# shield_puissance.net
KiCad netlist of a schematic drawn in EAGLE
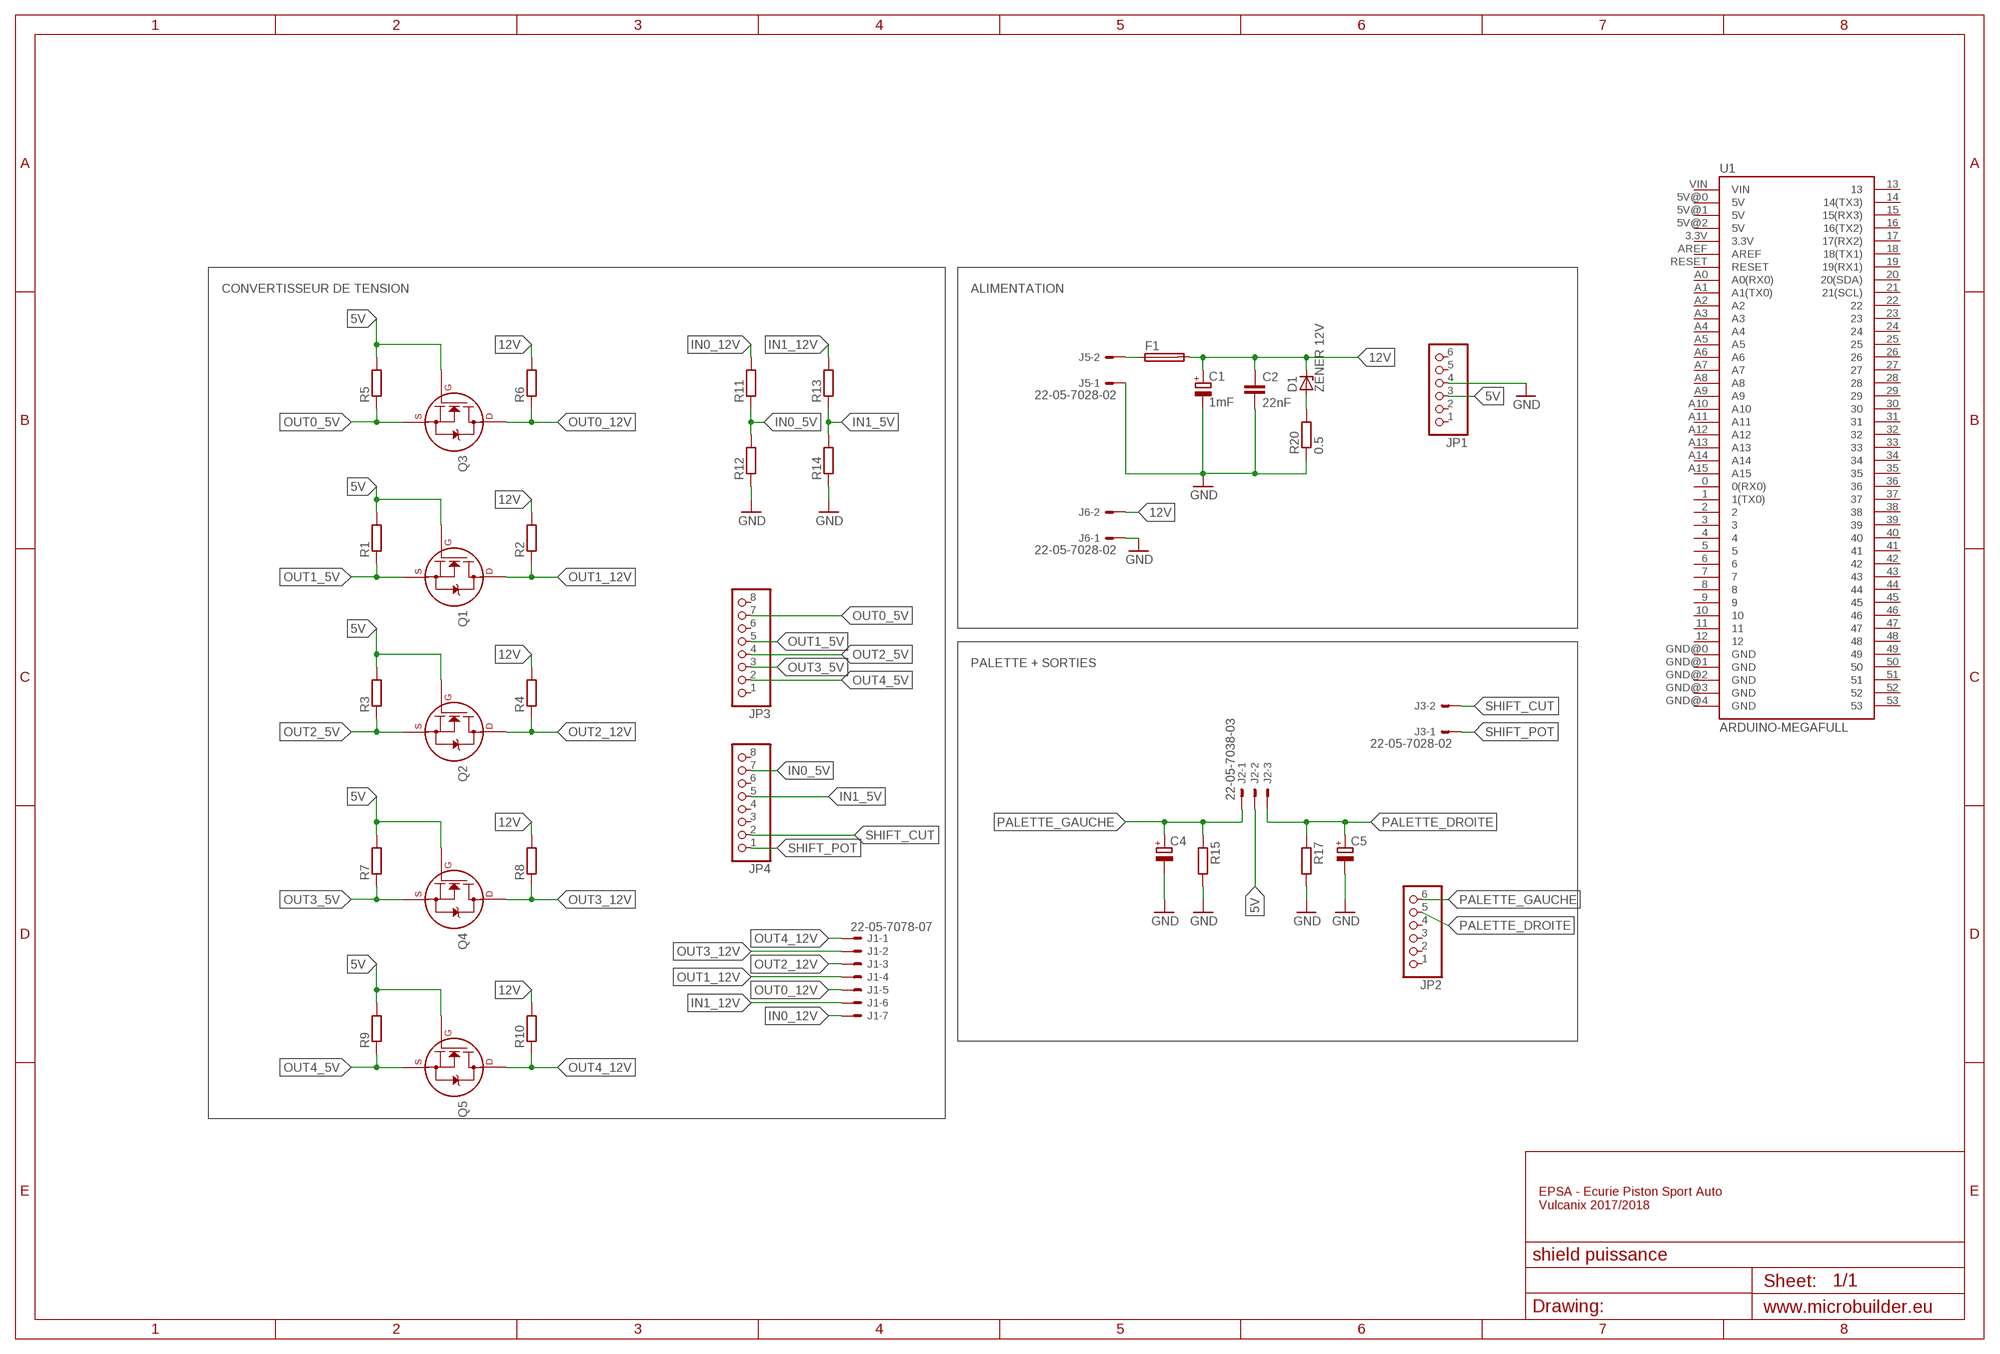
[diagram p0: schematic, sheet 1]

(export (version "E")
  (design (tool "Eeschema 10.0.6"))
  (components
    (comp (ref "C1")
      (value "1mF")
      (footprint "eagle-import:E2,5-6E")
      (libsource (lib "eagle-import") (part "CPOL-EUE2,5-6E"))
    )
    (comp (ref "C2")
      (value "22nF")
      (footprint "eagle-import:C025-025X050")
      (libsource (lib "eagle-import") (part "C-EU025-025X050"))
    )
    (comp (ref "C4")
      (value "CPOL-EUE2,5-6E")
      (footprint "eagle-import:E2,5-6E")
      (libsource (lib "eagle-import") (part "CPOL-EUE2,5-6E"))
    )
    (comp (ref "C5")
      (value "CPOL-EUE2,5-6E")
      (footprint "eagle-import:E2,5-6E")
      (libsource (lib "eagle-import") (part "CPOL-EUE2,5-6E"))
    )
    (comp (ref "D1")
      (value "ZENER 12V")
      (footprint "eagle-import:DO41Z10")
      (libsource (lib "eagle-import") (part "ZENER-DIODEDO41Z10"))
    )
    (comp (ref "F1")
      (value "SH25")
      (footprint "eagle-import:SH25")
      (fields (field (name "MF") "SCHURTER") (field (name "MPN") "0031.8211"))
      (libsource (lib "eagle-import") (part "SH25"))
    )
    (comp (ref "J1")
      (value "22-05-7078-07")
      (footprint "eagle-import:7395-07")
      (libsource (lib "eagle-import") (part "22-?-0705-7078"))
    )
    (comp (ref "J2")
      (value "22-05-7038-03")
      (footprint "eagle-import:7395-03")
      (libsource (lib "eagle-import") (part "22-?-0305-7038"))
    )
    (comp (ref "J3")
      (value "22-05-7028-02")
      (footprint "eagle-import:7395-02")
      (libsource (lib "eagle-import") (part "22-?-0205-7028"))
    )
    (comp (ref "J5")
      (value "22-05-7028-02")
      (footprint "eagle-import:7395-02")
      (libsource (lib "eagle-import") (part "22-?-0205-7028"))
    )
    (comp (ref "J6")
      (value "22-05-7028-02")
      (footprint "eagle-import:7395-02")
      (libsource (lib "eagle-import") (part "22-?-0205-7028"))
    )
    (comp (ref "JP1")
      (value "HEADER-1X6")
      (footprint "eagle-import:1X06_OVAL")
      (libsource (lib "eagle-import") (part "HEADER-1X6"))
    )
    (comp (ref "JP2")
      (value "HEADER-1X6")
      (footprint "eagle-import:1X06_OVAL")
      (libsource (lib "eagle-import") (part "HEADER-1X6"))
    )
    (comp (ref "JP3")
      (value "HEADER-1X8")
      (footprint "eagle-import:1X08_OVAL")
      (libsource (lib "eagle-import") (part "HEADER-1X8"))
    )
    (comp (ref "JP4")
      (value "HEADER-1X8")
      (footprint "eagle-import:1X08_OVAL")
      (libsource (lib "eagle-import") (part "HEADER-1X8"))
    )
    (comp (ref "Q1")
      (value "2N7000_TO92")
      (footprint "eagle-import:TO-92")
      (libsource (lib "eagle-import") (part "2N700_TO920"))
    )
    (comp (ref "Q2")
      (value "2N7000_TO92")
      (footprint "eagle-import:TO-92")
      (libsource (lib "eagle-import") (part "2N700_TO920"))
    )
    (comp (ref "Q3")
      (value "2N7000_TO92")
      (footprint "eagle-import:TO-92")
      (libsource (lib "eagle-import") (part "2N700_TO920"))
    )
    (comp (ref "Q4")
      (value "2N7000_TO92")
      (footprint "eagle-import:TO-92")
      (libsource (lib "eagle-import") (part "2N700_TO920"))
    )
    (comp (ref "Q5")
      (value "2N7000_TO92")
      (footprint "eagle-import:TO-92")
      (libsource (lib "eagle-import") (part "2N700_TO920"))
    )
    (comp (ref "R1")
      (value "R-EU_0204/7")
      (footprint "eagle-import:0204_7")
      (libsource (lib "eagle-import") (part "R-EU_0204/7"))
    )
    (comp (ref "R2")
      (value "R-EU_0204/7")
      (footprint "eagle-import:0204_7")
      (libsource (lib "eagle-import") (part "R-EU_0204/7"))
    )
    (comp (ref "R3")
      (value "R-EU_0204/7")
      (footprint "eagle-import:0204_7")
      (libsource (lib "eagle-import") (part "R-EU_0204/7"))
    )
    (comp (ref "R4")
      (value "R-EU_0204/7")
      (footprint "eagle-import:0204_7")
      (libsource (lib "eagle-import") (part "R-EU_0204/7"))
    )
    (comp (ref "R5")
      (value "R-EU_0204/7")
      (footprint "eagle-import:0204_7")
      (libsource (lib "eagle-import") (part "R-EU_0204/7"))
    )
    (comp (ref "R6")
      (value "R-EU_0204/7")
      (footprint "eagle-import:0204_7")
      (libsource (lib "eagle-import") (part "R-EU_0204/7"))
    )
    (comp (ref "R7")
      (value "R-EU_0204/7")
      (footprint "eagle-import:0204_7")
      (libsource (lib "eagle-import") (part "R-EU_0204/7"))
    )
    (comp (ref "R8")
      (value "R-EU_0204/7")
      (footprint "eagle-import:0204_7")
      (libsource (lib "eagle-import") (part "R-EU_0204/7"))
    )
    (comp (ref "R9")
      (value "R-EU_0204/7")
      (footprint "eagle-import:0204_7")
      (libsource (lib "eagle-import") (part "R-EU_0204/7"))
    )
    (comp (ref "R10")
      (value "R-EU_0204/7")
      (footprint "eagle-import:0204_7")
      (libsource (lib "eagle-import") (part "R-EU_0204/7"))
    )
    (comp (ref "R11")
      (value "R-EU_0204/7")
      (footprint "eagle-import:0204_7")
      (libsource (lib "eagle-import") (part "R-EU_0204/7"))
    )
    (comp (ref "R12")
      (value "R-EU_0204/7")
      (footprint "eagle-import:0204_7")
      (libsource (lib "eagle-import") (part "R-EU_0204/7"))
    )
    (comp (ref "R13")
      (value "R-EU_0204/7")
      (footprint "eagle-import:0204_7")
      (libsource (lib "eagle-import") (part "R-EU_0204/7"))
    )
    (comp (ref "R14")
      (value "R-EU_0204/7")
      (footprint "eagle-import:0204_7")
      (libsource (lib "eagle-import") (part "R-EU_0204/7"))
    )
    (comp (ref "R15")
      (value "R-EU_0204/7")
      (footprint "eagle-import:0204_7")
      (libsource (lib "eagle-import") (part "R-EU_0204/7"))
    )
    (comp (ref "R17")
      (value "R-EU_0204/7")
      (footprint "eagle-import:0204_7")
      (libsource (lib "eagle-import") (part "R-EU_0204/7"))
    )
    (comp (ref "R20")
      (value "0.5")
      (footprint "eagle-import:0309_12")
      (libsource (lib "eagle-import") (part "R-EU_0309/12"))
    )
    (comp (ref "U1")
      (value "ARDUINO-MEGAFULL")
      (footprint "eagle-import:ARDUINO_MEGA")
      (libsource (lib "eagle-import") (part "ARDUINO-MEGAFULL"))
    )
  )
  (nets
    (net (code "1") (name "5V") (class "Default")
      (node (ref "J2") (pin "2") (pinfunction "S_2") (pintype "passive"))
      (node (ref "JP1") (pin "3") (pinfunction "3_3") (pintype "passive"))
      (node (ref "Q1") (pin "2") (pinfunction "G_2") (pintype "tri_state"))
      (node (ref "Q2") (pin "2") (pinfunction "G_2") (pintype "tri_state"))
      (node (ref "Q3") (pin "2") (pinfunction "G_2") (pintype "tri_state"))
      (node (ref "Q4") (pin "2") (pinfunction "G_2") (pintype "tri_state"))
      (node (ref "Q5") (pin "2") (pinfunction "G_2") (pintype "tri_state"))
      (node (ref "R1") (pin "2") (pinfunction "2_2") (pintype "passive"))
      (node (ref "R3") (pin "2") (pinfunction "2_2") (pintype "passive"))
      (node (ref "R5") (pin "2") (pinfunction "2_2") (pintype "passive"))
      (node (ref "R7") (pin "2") (pinfunction "2_2") (pintype "passive"))
      (node (ref "R9") (pin "2") (pinfunction "2_2") (pintype "passive"))
    )
    (net (code "2") (name "12V") (class "Default")
      (node (ref "C1") (pin "+") (pinfunction "+_+") (pintype "passive"))
      (node (ref "C2") (pin "1") (pinfunction "1_1") (pintype "passive"))
      (node (ref "D1") (pin "C") (pinfunction "C_C") (pintype "passive"))
      (node (ref "F1") (pin "2") (pinfunction "2_2") (pintype "passive"))
      (node (ref "J6") (pin "2") (pinfunction "S_2") (pintype "passive"))
      (node (ref "R10") (pin "2") (pinfunction "2_2") (pintype "passive"))
      (node (ref "R2") (pin "2") (pinfunction "2_2") (pintype "passive"))
      (node (ref "R4") (pin "2") (pinfunction "2_2") (pintype "passive"))
      (node (ref "R6") (pin "2") (pinfunction "2_2") (pintype "passive"))
      (node (ref "R8") (pin "2") (pinfunction "2_2") (pintype "passive"))
    )
    (net (code "3") (name "GND") (class "Default")
      (node (ref "C1") (pin "-") (pinfunction "-_-") (pintype "passive"))
      (node (ref "C2") (pin "2") (pinfunction "2_2") (pintype "passive"))
      (node (ref "C4") (pin "-") (pinfunction "-_-") (pintype "passive"))
      (node (ref "C5") (pin "-") (pinfunction "-_-") (pintype "passive"))
      (node (ref "J5") (pin "1") (pinfunction "S_1") (pintype "passive"))
      (node (ref "J6") (pin "1") (pinfunction "S_1") (pintype "passive"))
      (node (ref "JP1") (pin "4") (pinfunction "4_4") (pintype "passive"))
      (node (ref "R12") (pin "1") (pinfunction "1_1") (pintype "passive"))
      (node (ref "R14") (pin "1") (pinfunction "1_1") (pintype "passive"))
      (node (ref "R15") (pin "2") (pinfunction "2_2") (pintype "passive"))
      (node (ref "R17") (pin "2") (pinfunction "2_2") (pintype "passive"))
      (node (ref "R20") (pin "1") (pinfunction "1_1") (pintype "passive"))
    )
    (net (code "4") (name "IN0_5V") (class "Default")
      (node (ref "JP4") (pin "7") (pinfunction "7_7") (pintype "passive"))
      (node (ref "R11") (pin "1") (pinfunction "1_1") (pintype "passive"))
      (node (ref "R12") (pin "2") (pinfunction "2_2") (pintype "passive"))
    )
    (net (code "5") (name "IN0_12V") (class "Default")
      (node (ref "J1") (pin "7") (pinfunction "S_7") (pintype "passive"))
      (node (ref "R11") (pin "2") (pinfunction "2_2") (pintype "passive"))
    )
    (net (code "6") (name "IN1_5V") (class "Default")
      (node (ref "JP4") (pin "5") (pinfunction "5_5") (pintype "passive"))
      (node (ref "R13") (pin "1") (pinfunction "1_1") (pintype "passive"))
      (node (ref "R14") (pin "2") (pinfunction "2_2") (pintype "passive"))
    )
    (net (code "7") (name "IN1_12V") (class "Default")
      (node (ref "J1") (pin "6") (pinfunction "S_6") (pintype "passive"))
      (node (ref "R13") (pin "2") (pinfunction "2_2") (pintype "passive"))
    )
    (net (code "8") (name "Net-(D1-PadA)") (class "Default")
      (node (ref "D1") (pin "A") (pinfunction "A_A") (pintype "passive"))
      (node (ref "R20") (pin "2") (pinfunction "2_2") (pintype "passive"))
    )
    (net (code "9") (name "Net-(J5B-S)") (class "Default")
      (node (ref "F1") (pin "1") (pinfunction "1_1") (pintype "passive"))
      (node (ref "J5") (pin "2") (pinfunction "S_2") (pintype "passive"))
    )
    (net (code "10") (name "OUT0_5V") (class "Default")
      (node (ref "JP3") (pin "7") (pinfunction "7_7") (pintype "passive"))
      (node (ref "Q3") (pin "1") (pinfunction "S_1") (pintype "bidirectional"))
      (node (ref "R5") (pin "1") (pinfunction "1_1") (pintype "passive"))
    )
    (net (code "11") (name "OUT0_12V") (class "Default")
      (node (ref "J1") (pin "5") (pinfunction "S_5") (pintype "passive"))
      (node (ref "Q3") (pin "3") (pinfunction "D_3") (pintype "bidirectional"))
      (node (ref "R6") (pin "1") (pinfunction "1_1") (pintype "passive"))
    )
    (net (code "12") (name "OUT1_5V") (class "Default")
      (node (ref "JP3") (pin "5") (pinfunction "5_5") (pintype "passive"))
      (node (ref "Q1") (pin "1") (pinfunction "S_1") (pintype "bidirectional"))
      (node (ref "R1") (pin "1") (pinfunction "1_1") (pintype "passive"))
    )
    (net (code "13") (name "OUT1_12V") (class "Default")
      (node (ref "J1") (pin "4") (pinfunction "S_4") (pintype "passive"))
      (node (ref "Q1") (pin "3") (pinfunction "D_3") (pintype "bidirectional"))
      (node (ref "R2") (pin "1") (pinfunction "1_1") (pintype "passive"))
    )
    (net (code "14") (name "OUT2_5V") (class "Default")
      (node (ref "JP3") (pin "4") (pinfunction "4_4") (pintype "passive"))
      (node (ref "Q2") (pin "1") (pinfunction "S_1") (pintype "bidirectional"))
      (node (ref "R3") (pin "1") (pinfunction "1_1") (pintype "passive"))
    )
    (net (code "15") (name "OUT2_12V") (class "Default")
      (node (ref "J1") (pin "3") (pinfunction "S_3") (pintype "passive"))
      (node (ref "Q2") (pin "3") (pinfunction "D_3") (pintype "bidirectional"))
      (node (ref "R4") (pin "1") (pinfunction "1_1") (pintype "passive"))
    )
    (net (code "16") (name "OUT3_5V") (class "Default")
      (node (ref "JP3") (pin "3") (pinfunction "3_3") (pintype "passive"))
      (node (ref "Q4") (pin "1") (pinfunction "S_1") (pintype "bidirectional"))
      (node (ref "R7") (pin "1") (pinfunction "1_1") (pintype "passive"))
    )
    (net (code "17") (name "OUT3_12V") (class "Default")
      (node (ref "J1") (pin "2") (pinfunction "S_2") (pintype "passive"))
      (node (ref "Q4") (pin "3") (pinfunction "D_3") (pintype "bidirectional"))
      (node (ref "R8") (pin "1") (pinfunction "1_1") (pintype "passive"))
    )
    (net (code "18") (name "OUT4_5V") (class "Default")
      (node (ref "JP3") (pin "2") (pinfunction "2_2") (pintype "passive"))
      (node (ref "Q5") (pin "1") (pinfunction "S_1") (pintype "bidirectional"))
      (node (ref "R9") (pin "1") (pinfunction "1_1") (pintype "passive"))
    )
    (net (code "19") (name "OUT4_12V") (class "Default")
      (node (ref "J1") (pin "1") (pinfunction "S_1") (pintype "passive"))
      (node (ref "Q5") (pin "3") (pinfunction "D_3") (pintype "bidirectional"))
      (node (ref "R10") (pin "1") (pinfunction "1_1") (pintype "passive"))
    )
    (net (code "20") (name "PALETTE_DROITE") (class "Default")
      (node (ref "C5") (pin "+") (pinfunction "+_+") (pintype "passive"))
      (node (ref "J2") (pin "3") (pinfunction "S_3") (pintype "passive"))
      (node (ref "JP2") (pin "5") (pinfunction "5_5") (pintype "passive"))
      (node (ref "R17") (pin "1") (pinfunction "1_1") (pintype "passive"))
    )
    (net (code "21") (name "PALETTE_GAUCHE") (class "Default")
      (node (ref "C4") (pin "+") (pinfunction "+_+") (pintype "passive"))
      (node (ref "J2") (pin "1") (pinfunction "S_1") (pintype "passive"))
      (node (ref "JP2") (pin "6") (pinfunction "6_6") (pintype "passive"))
      (node (ref "R15") (pin "1") (pinfunction "1_1") (pintype "passive"))
    )
    (net (code "22") (name "SHIFT_CUT") (class "Default")
      (node (ref "J3") (pin "2") (pinfunction "S_2") (pintype "passive"))
      (node (ref "JP4") (pin "2") (pinfunction "2_2") (pintype "passive"))
    )
    (net (code "23") (name "SHIFT_POT") (class "Default")
      (node (ref "J3") (pin "1") (pinfunction "S_1") (pintype "passive"))
      (node (ref "JP4") (pin "1") (pinfunction "1_1") (pintype "passive"))
    )
    (net (code "24") (name "unconnected-(JP1-Pad1)") (class "Default")
      (node (ref "JP1") (pin "1") (pinfunction "1_1") (pintype "passive"))
    )
    (net (code "25") (name "unconnected-(JP1-Pad2)") (class "Default")
      (node (ref "JP1") (pin "2") (pinfunction "2_2") (pintype "passive"))
    )
    (net (code "26") (name "unconnected-(JP1-Pad5)") (class "Default")
      (node (ref "JP1") (pin "5") (pinfunction "5_5") (pintype "passive"))
    )
    (net (code "27") (name "unconnected-(JP1-Pad6)") (class "Default")
      (node (ref "JP1") (pin "6") (pinfunction "6_6") (pintype "passive"))
    )
    (net (code "28") (name "unconnected-(JP2-Pad1)") (class "Default")
      (node (ref "JP2") (pin "1") (pinfunction "1_1") (pintype "passive"))
    )
    (net (code "29") (name "unconnected-(JP2-Pad2)") (class "Default")
      (node (ref "JP2") (pin "2") (pinfunction "2_2") (pintype "passive"))
    )
    (net (code "30") (name "unconnected-(JP2-Pad3)") (class "Default")
      (node (ref "JP2") (pin "3") (pinfunction "3_3") (pintype "passive"))
    )
    (net (code "31") (name "unconnected-(JP2-Pad4)") (class "Default")
      (node (ref "JP2") (pin "4") (pinfunction "4_4") (pintype "passive"))
    )
    (net (code "32") (name "unconnected-(JP3-Pad1)") (class "Default")
      (node (ref "JP3") (pin "1") (pinfunction "1_1") (pintype "passive"))
    )
    (net (code "33") (name "unconnected-(JP3-Pad6)") (class "Default")
      (node (ref "JP3") (pin "6") (pinfunction "6_6") (pintype "passive"))
    )
    (net (code "34") (name "unconnected-(JP3-Pad8)") (class "Default")
      (node (ref "JP3") (pin "8") (pinfunction "8_8") (pintype "passive"))
    )
    (net (code "35") (name "unconnected-(JP4-Pad3)") (class "Default")
      (node (ref "JP4") (pin "3") (pinfunction "3_3") (pintype "passive"))
    )
    (net (code "36") (name "unconnected-(JP4-Pad4)") (class "Default")
      (node (ref "JP4") (pin "4") (pinfunction "4_4") (pintype "passive"))
    )
    (net (code "37") (name "unconnected-(JP4-Pad6)") (class "Default")
      (node (ref "JP4") (pin "6") (pinfunction "6_6") (pintype "passive"))
    )
    (net (code "38") (name "unconnected-(JP4-Pad8)") (class "Default")
      (node (ref "JP4") (pin "8") (pinfunction "8_8") (pintype "passive"))
    )
    (net (code "39") (name "unconnected-(U1-0(RX0)-Pad0)") (class "Default")
      (node (ref "U1") (pin "0") (pinfunction "0(RX0)_0") (pintype "bidirectional"))
    )
    (net (code "40") (name "unconnected-(U1-1(TX0)-Pad1)") (class "Default")
      (node (ref "U1") (pin "1") (pinfunction "1(TX0)_1") (pintype "bidirectional"))
    )
    (net (code "41") (name "unconnected-(U1-5V-Pad5V@0)") (class "Default")
      (node (ref "U1") (pin "5V@0") (pinfunction "5V_5V@0") (pintype "bidirectional"))
    )
    (net (code "42") (name "unconnected-(U1-5V-Pad5V@1)") (class "Default")
      (node (ref "U1") (pin "5V@1") (pinfunction "5V_5V@1") (pintype "bidirectional"))
    )
    (net (code "43") (name "unconnected-(U1-5V-Pad5V@2)") (class "Default")
      (node (ref "U1") (pin "5V@2") (pinfunction "5V_5V@2") (pintype "bidirectional"))
    )
    (net (code "44") (name "unconnected-(U1-14(TX3)-Pad14)") (class "Default")
      (node (ref "U1") (pin "14") (pinfunction "14(TX3)_14") (pintype "bidirectional"))
    )
    (net (code "45") (name "unconnected-(U1-15(RX3)-Pad15)") (class "Default")
      (node (ref "U1") (pin "15") (pinfunction "15(RX3)_15") (pintype "bidirectional"))
    )
    (net (code "46") (name "unconnected-(U1-16(TX2)-Pad16)") (class "Default")
      (node (ref "U1") (pin "16") (pinfunction "16(TX2)_16") (pintype "bidirectional"))
    )
    (net (code "47") (name "unconnected-(U1-17(RX2)-Pad17)") (class "Default")
      (node (ref "U1") (pin "17") (pinfunction "17(RX2)_17") (pintype "bidirectional"))
    )
    (net (code "48") (name "unconnected-(U1-18(TX1)-Pad18)") (class "Default")
      (node (ref "U1") (pin "18") (pinfunction "18(TX1)_18") (pintype "bidirectional"))
    )
    (net (code "49") (name "unconnected-(U1-19(RX1)-Pad19)") (class "Default")
      (node (ref "U1") (pin "19") (pinfunction "19(RX1)_19") (pintype "bidirectional"))
    )
    (net (code "50") (name "unconnected-(U1-20(SDA)-Pad20)") (class "Default")
      (node (ref "U1") (pin "20") (pinfunction "20(SDA)_20") (pintype "bidirectional"))
    )
    (net (code "51") (name "unconnected-(U1-21(SCL)-Pad21)") (class "Default")
      (node (ref "U1") (pin "21") (pinfunction "21(SCL)_21") (pintype "bidirectional"))
    )
    (net (code "52") (name "unconnected-(U1-A0(RX0)-PadA0)") (class "Default")
      (node (ref "U1") (pin "A0") (pinfunction "A0(RX0)_A0") (pintype "bidirectional"))
    )
    (net (code "53") (name "unconnected-(U1-A1(TX0)-PadA1)") (class "Default")
      (node (ref "U1") (pin "A1") (pinfunction "A1(TX0)_A1") (pintype "bidirectional"))
    )
    (net (code "54") (name "unconnected-(U1-GND-PadGND@0)") (class "Default")
      (node (ref "U1") (pin "GND@0") (pinfunction "GND_GND@0") (pintype "bidirectional"))
    )
    (net (code "55") (name "unconnected-(U1-GND-PadGND@1)") (class "Default")
      (node (ref "U1") (pin "GND@1") (pinfunction "GND_GND@1") (pintype "bidirectional"))
    )
    (net (code "56") (name "unconnected-(U1-GND-PadGND@2)") (class "Default")
      (node (ref "U1") (pin "GND@2") (pinfunction "GND_GND@2") (pintype "bidirectional"))
    )
    (net (code "57") (name "unconnected-(U1-GND-PadGND@3)") (class "Default")
      (node (ref "U1") (pin "GND@3") (pinfunction "GND_GND@3") (pintype "bidirectional"))
    )
    (net (code "58") (name "unconnected-(U1-GND-PadGND@4)") (class "Default")
      (node (ref "U1") (pin "GND@4") (pinfunction "GND_GND@4") (pintype "bidirectional"))
    )
    (net (code "59") (name "unconnected-(U1-Pad2)") (class "Default")
      (node (ref "U1") (pin "2") (pinfunction "2_2") (pintype "bidirectional"))
    )
    (net (code "60") (name "unconnected-(U1-Pad3)") (class "Default")
      (node (ref "U1") (pin "3") (pinfunction "3_3") (pintype "bidirectional"))
    )
    (net (code "61") (name "unconnected-(U1-Pad3.3V)") (class "Default")
      (node (ref "U1") (pin "3.3V") (pinfunction "3.3V_3.3V") (pintype "bidirectional"))
    )
    (net (code "62") (name "unconnected-(U1-Pad4)") (class "Default")
      (node (ref "U1") (pin "4") (pinfunction "4_4") (pintype "bidirectional"))
    )
    (net (code "63") (name "unconnected-(U1-Pad5)") (class "Default")
      (node (ref "U1") (pin "5") (pinfunction "5_5") (pintype "bidirectional"))
    )
    (net (code "64") (name "unconnected-(U1-Pad6)") (class "Default")
      (node (ref "U1") (pin "6") (pinfunction "6_6") (pintype "bidirectional"))
    )
    (net (code "65") (name "unconnected-(U1-Pad7)") (class "Default")
      (node (ref "U1") (pin "7") (pinfunction "7_7") (pintype "bidirectional"))
    )
    (net (code "66") (name "unconnected-(U1-Pad8)") (class "Default")
      (node (ref "U1") (pin "8") (pinfunction "8_8") (pintype "bidirectional"))
    )
    (net (code "67") (name "unconnected-(U1-Pad9)") (class "Default")
      (node (ref "U1") (pin "9") (pinfunction "9_9") (pintype "bidirectional"))
    )
    (net (code "68") (name "unconnected-(U1-Pad10)") (class "Default")
      (node (ref "U1") (pin "10") (pinfunction "10_10") (pintype "bidirectional"))
    )
    (net (code "69") (name "unconnected-(U1-Pad11)") (class "Default")
      (node (ref "U1") (pin "11") (pinfunction "11_11") (pintype "bidirectional"))
    )
    (net (code "70") (name "unconnected-(U1-Pad12)") (class "Default")
      (node (ref "U1") (pin "12") (pinfunction "12_12") (pintype "bidirectional"))
    )
    (net (code "71") (name "unconnected-(U1-Pad13)") (class "Default")
      (node (ref "U1") (pin "13") (pinfunction "13_13") (pintype "bidirectional"))
    )
    (net (code "72") (name "unconnected-(U1-Pad22)") (class "Default")
      (node (ref "U1") (pin "22") (pinfunction "22_22") (pintype "bidirectional"))
    )
    (net (code "73") (name "unconnected-(U1-Pad23)") (class "Default")
      (node (ref "U1") (pin "23") (pinfunction "23_23") (pintype "bidirectional"))
    )
    (net (code "74") (name "unconnected-(U1-Pad24)") (class "Default")
      (node (ref "U1") (pin "24") (pinfunction "24_24") (pintype "bidirectional"))
    )
    (net (code "75") (name "unconnected-(U1-Pad25)") (class "Default")
      (node (ref "U1") (pin "25") (pinfunction "25_25") (pintype "bidirectional"))
    )
    (net (code "76") (name "unconnected-(U1-Pad26)") (class "Default")
      (node (ref "U1") (pin "26") (pinfunction "26_26") (pintype "bidirectional"))
    )
    (net (code "77") (name "unconnected-(U1-Pad27)") (class "Default")
      (node (ref "U1") (pin "27") (pinfunction "27_27") (pintype "bidirectional"))
    )
    (net (code "78") (name "unconnected-(U1-Pad28)") (class "Default")
      (node (ref "U1") (pin "28") (pinfunction "28_28") (pintype "bidirectional"))
    )
    (net (code "79") (name "unconnected-(U1-Pad29)") (class "Default")
      (node (ref "U1") (pin "29") (pinfunction "29_29") (pintype "bidirectional"))
    )
    (net (code "80") (name "unconnected-(U1-Pad30)") (class "Default")
      (node (ref "U1") (pin "30") (pinfunction "30_30") (pintype "bidirectional"))
    )
    (net (code "81") (name "unconnected-(U1-Pad31)") (class "Default")
      (node (ref "U1") (pin "31") (pinfunction "31_31") (pintype "bidirectional"))
    )
    (net (code "82") (name "unconnected-(U1-Pad32)") (class "Default")
      (node (ref "U1") (pin "32") (pinfunction "32_32") (pintype "bidirectional"))
    )
    (net (code "83") (name "unconnected-(U1-Pad33)") (class "Default")
      (node (ref "U1") (pin "33") (pinfunction "33_33") (pintype "bidirectional"))
    )
    (net (code "84") (name "unconnected-(U1-Pad34)") (class "Default")
      (node (ref "U1") (pin "34") (pinfunction "34_34") (pintype "bidirectional"))
    )
    (net (code "85") (name "unconnected-(U1-Pad35)") (class "Default")
      (node (ref "U1") (pin "35") (pinfunction "35_35") (pintype "bidirectional"))
    )
    (net (code "86") (name "unconnected-(U1-Pad36)") (class "Default")
      (node (ref "U1") (pin "36") (pinfunction "36_36") (pintype "bidirectional"))
    )
    (net (code "87") (name "unconnected-(U1-Pad37)") (class "Default")
      (node (ref "U1") (pin "37") (pinfunction "37_37") (pintype "bidirectional"))
    )
    (net (code "88") (name "unconnected-(U1-Pad38)") (class "Default")
      (node (ref "U1") (pin "38") (pinfunction "38_38") (pintype "bidirectional"))
    )
    (net (code "89") (name "unconnected-(U1-Pad39)") (class "Default")
      (node (ref "U1") (pin "39") (pinfunction "39_39") (pintype "bidirectional"))
    )
    (net (code "90") (name "unconnected-(U1-Pad40)") (class "Default")
      (node (ref "U1") (pin "40") (pinfunction "40_40") (pintype "bidirectional"))
    )
    (net (code "91") (name "unconnected-(U1-Pad41)") (class "Default")
      (node (ref "U1") (pin "41") (pinfunction "41_41") (pintype "bidirectional"))
    )
    (net (code "92") (name "unconnected-(U1-Pad42)") (class "Default")
      (node (ref "U1") (pin "42") (pinfunction "42_42") (pintype "bidirectional"))
    )
    (net (code "93") (name "unconnected-(U1-Pad43)") (class "Default")
      (node (ref "U1") (pin "43") (pinfunction "43_43") (pintype "bidirectional"))
    )
    (net (code "94") (name "unconnected-(U1-Pad44)") (class "Default")
      (node (ref "U1") (pin "44") (pinfunction "44_44") (pintype "bidirectional"))
    )
    (net (code "95") (name "unconnected-(U1-Pad45)") (class "Default")
      (node (ref "U1") (pin "45") (pinfunction "45_45") (pintype "bidirectional"))
    )
    (net (code "96") (name "unconnected-(U1-Pad46)") (class "Default")
      (node (ref "U1") (pin "46") (pinfunction "46_46") (pintype "bidirectional"))
    )
    (net (code "97") (name "unconnected-(U1-Pad47)") (class "Default")
      (node (ref "U1") (pin "47") (pinfunction "47_47") (pintype "bidirectional"))
    )
    (net (code "98") (name "unconnected-(U1-Pad48)") (class "Default")
      (node (ref "U1") (pin "48") (pinfunction "48_48") (pintype "bidirectional"))
    )
    (net (code "99") (name "unconnected-(U1-Pad49)") (class "Default")
      (node (ref "U1") (pin "49") (pinfunction "49_49") (pintype "bidirectional"))
    )
    (net (code "100") (name "unconnected-(U1-Pad50)") (class "Default")
      (node (ref "U1") (pin "50") (pinfunction "50_50") (pintype "bidirectional"))
    )
    (net (code "101") (name "unconnected-(U1-Pad51)") (class "Default")
      (node (ref "U1") (pin "51") (pinfunction "51_51") (pintype "bidirectional"))
    )
    (net (code "102") (name "unconnected-(U1-Pad52)") (class "Default")
      (node (ref "U1") (pin "52") (pinfunction "52_52") (pintype "bidirectional"))
    )
    (net (code "103") (name "unconnected-(U1-Pad53)") (class "Default")
      (node (ref "U1") (pin "53") (pinfunction "53_53") (pintype "bidirectional"))
    )
    (net (code "104") (name "unconnected-(U1-PadA2)") (class "Default")
      (node (ref "U1") (pin "A2") (pinfunction "A2_A2") (pintype "bidirectional"))
    )
    (net (code "105") (name "unconnected-(U1-PadA3)") (class "Default")
      (node (ref "U1") (pin "A3") (pinfunction "A3_A3") (pintype "bidirectional"))
    )
    (net (code "106") (name "unconnected-(U1-PadA4)") (class "Default")
      (node (ref "U1") (pin "A4") (pinfunction "A4_A4") (pintype "bidirectional"))
    )
    (net (code "107") (name "unconnected-(U1-PadA5)") (class "Default")
      (node (ref "U1") (pin "A5") (pinfunction "A5_A5") (pintype "bidirectional"))
    )
    (net (code "108") (name "unconnected-(U1-PadA6)") (class "Default")
      (node (ref "U1") (pin "A6") (pinfunction "A6_A6") (pintype "bidirectional"))
    )
    (net (code "109") (name "unconnected-(U1-PadA7)") (class "Default")
      (node (ref "U1") (pin "A7") (pinfunction "A7_A7") (pintype "bidirectional"))
    )
    (net (code "110") (name "unconnected-(U1-PadA8)") (class "Default")
      (node (ref "U1") (pin "A8") (pinfunction "A8_A8") (pintype "bidirectional"))
    )
    (net (code "111") (name "unconnected-(U1-PadA9)") (class "Default")
      (node (ref "U1") (pin "A9") (pinfunction "A9_A9") (pintype "bidirectional"))
    )
    (net (code "112") (name "unconnected-(U1-PadA10)") (class "Default")
      (node (ref "U1") (pin "A10") (pinfunction "A10_A10") (pintype "bidirectional"))
    )
    (net (code "113") (name "unconnected-(U1-PadA11)") (class "Default")
      (node (ref "U1") (pin "A11") (pinfunction "A11_A11") (pintype "bidirectional"))
    )
    (net (code "114") (name "unconnected-(U1-PadA12)") (class "Default")
      (node (ref "U1") (pin "A12") (pinfunction "A12_A12") (pintype "bidirectional"))
    )
    (net (code "115") (name "unconnected-(U1-PadA13)") (class "Default")
      (node (ref "U1") (pin "A13") (pinfunction "A13_A13") (pintype "bidirectional"))
    )
    (net (code "116") (name "unconnected-(U1-PadA14)") (class "Default")
      (node (ref "U1") (pin "A14") (pinfunction "A14_A14") (pintype "bidirectional"))
    )
    (net (code "117") (name "unconnected-(U1-PadA15)") (class "Default")
      (node (ref "U1") (pin "A15") (pinfunction "A15_A15") (pintype "bidirectional"))
    )
    (net (code "118") (name "unconnected-(U1-PadAREF)") (class "Default")
      (node (ref "U1") (pin "AREF") (pinfunction "AREF_AREF") (pintype "bidirectional"))
    )
    (net (code "119") (name "unconnected-(U1-PadRESET)") (class "Default")
      (node (ref "U1") (pin "RESET") (pinfunction "RESET_RESET") (pintype "bidirectional"))
    )
    (net (code "120") (name "unconnected-(U1-PadVIN)") (class "Default")
      (node (ref "U1") (pin "VIN") (pinfunction "VIN_VIN") (pintype "bidirectional"))
    )
  )
)
